# 05_SiC_Nanosecond_Stage.net
KiCad netlist of a schematic drawn in Altium Designer
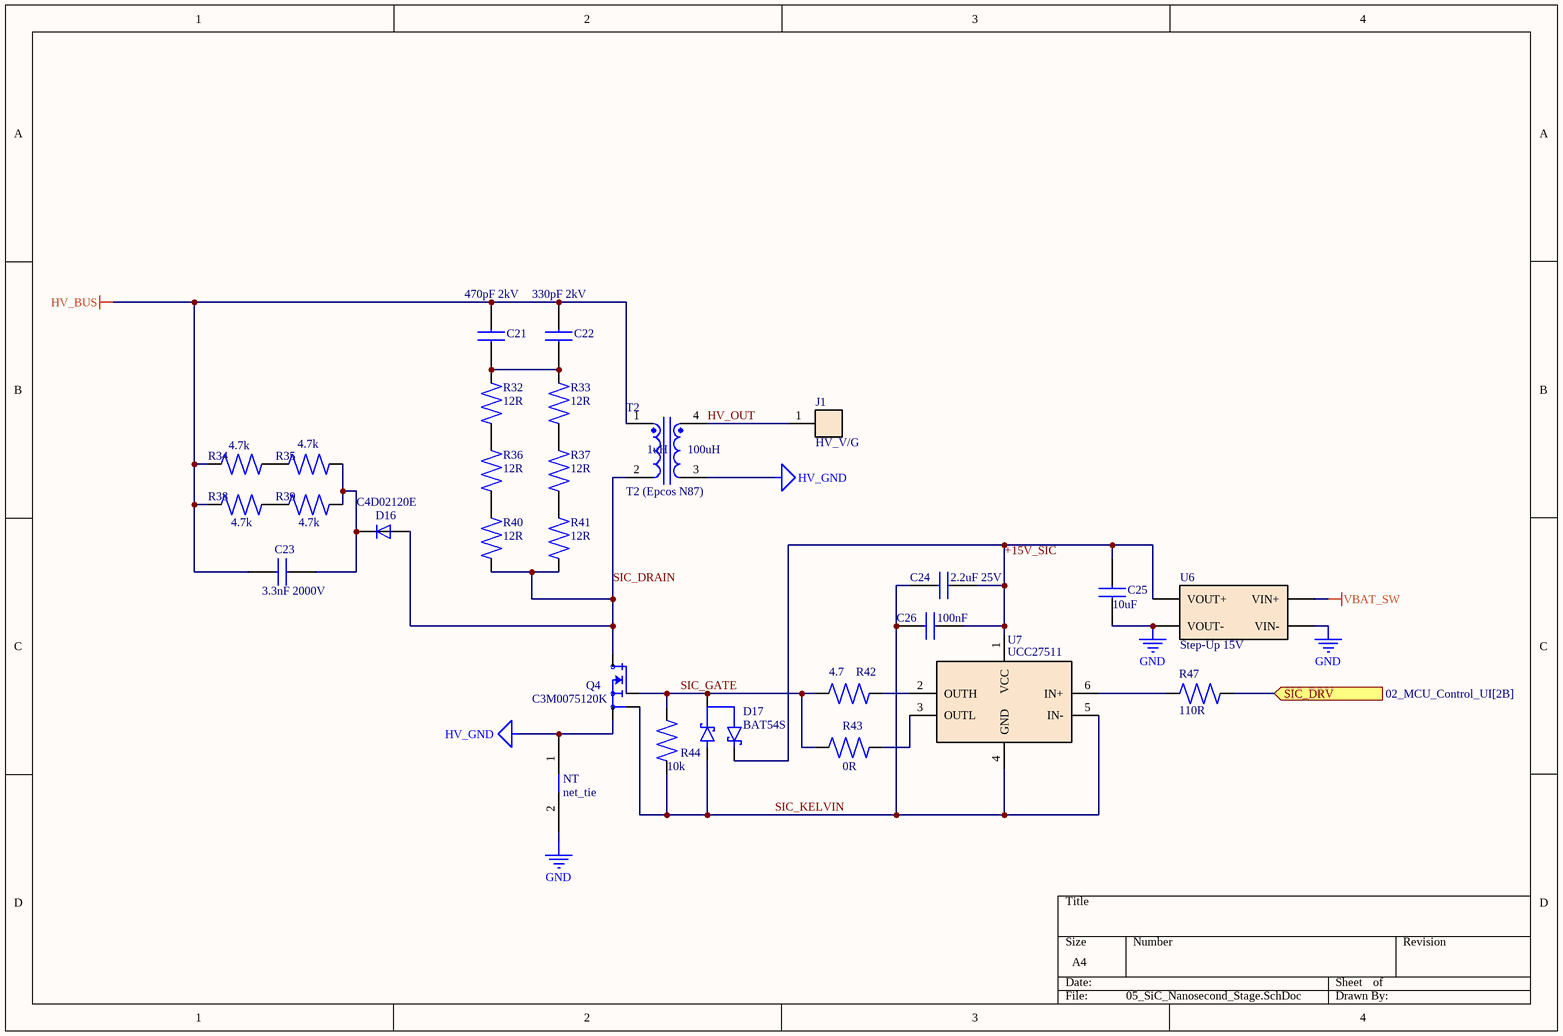
[diagram p0: 05_SiC_Nanosecond_Stage.SchDoc]

(export (version "E")
  (design (tool "Eeschema 10.0.6"))
  (components
    (comp (ref "C21")
      (value "470pF 2kV")
      (footprint "CAP_FILM_P15.0_CBB81_HEAVY_DUTY")
      (description "Capacitor Film, Polypropylene (PP), 470 pF, 2000 VDC, ±5%, Radial THT, Pitch 15mm, CBB81")
      (libsource (lib "Schlib1") (part "CAP_FILM_CBB81_470pF_2000V"))
    )
    (comp (ref "C22")
      (value "330pF 2kV")
      (footprint "CAP_FILM_P15.0_CBB81_HEAVY_DUTY")
      (description "Capacitor Film, Polypropylene (PP), 330 pF, 2000 VDC, ±5%, Radial THT, Pitch 15mm, CBB81")
      (libsource (lib "Schlib1") (part "CAP_FILM_CBB81_330pF_2000V"))
    )
    (comp (ref "C23")
      (value "3.3nF 2000V")
      (footprint "CAP_FILM_P15.0_CBB81_HEAVY_DUTY")
      (libsource (lib "Schlib1") (part "CAP_FILM_CBB81_3.2nF_2000V"))
    )
    (comp (ref "C24")
      (value "2.2uF 25V")
      (footprint "CHIP_0805_SMD")
      (description "Capacitor MLCC, Ceramic, 2.2 uF, 25 V, ±10%, X7R, SMD 0805, Hitano Enterprise")
      (libsource (lib "Schlib1") (part "CAP_0805_2.2uF_25V_X7R"))
    )
    (comp (ref "C25")
      (value "10uF")
      (footprint "CHIP_0805_SMD")
      (description "Capacitor MLCC, Ceramic, 10 uF, 16 V, ±10%, X7R, SMD 0805, Hitano Enterprise")
      (libsource (lib "Schlib1") (part "CAP_0805_10uF_16V_X7R"))
    )
    (comp (ref "C26")
      (value "100nF")
      (footprint "CHIP_0603_SMD")
      (description "Capacitor MLCC, Ceramic, 100 nF, 50 V, ±10%, X7R, SMD 0603, Samsung Electro-Mechanics")
      (libsource (lib "Schlib1") (part "CAP_0603_100nF_50V_X7R"))
    )
    (comp (ref "D16")
      (value "C4D02120E")
      (footprint "TO-252-2L_DPAK_THERMAL")
      (description "SiC Schottky Diode, 1200V, 2A, Zero Recovery, TO-252-2 (DPAK), Pin 1: Anode, Pin 2: Cathode (Tab)")
      (libsource (lib "Schlib1") (part "DIODE_SIC_C4D02120E_TO252"))
    )
    (comp (ref "D17")
      (value "BAT54S")
      (footprint "SOT-23_3P_SMD")
      (libsource (lib "Schlib1") (part "DIODE_SCHOTTKY_BAT54S_SOT23"))
    )
    (comp (ref "J1")
      (value "HV_V/G")
      (footprint "PAD_HV_UL3239_28AWG_ROUND")
      (description "High Voltage Solder Pad / Wire Terminal, Single Pin THT, Hole D=1.8mm, Pad D=3.5mm")
      (libsource (lib "Schlib1") (part "PAD_HV_TERMINAL_1P"))
    )
    (comp (ref "NT")
      (value "net_tie")
      (footprint "NET_TIE_SMD")
      (libsource (lib "Schlib1") (part "NET_TIE_SMD"))
    )
    (comp (ref "Q4")
      (value "C3M0075120K")
      (footprint "TO-247-4_WOLFSPEED_SLOTTED_VERT")
      (description "SiC Power MOSFET N-CH, 1200V, 30A, 75 mOhm, Kelvin Source, TO-247-4, Wolfspeed / Cree")
      (libsource (lib "Schlib1") (part "MOSFET_N-CH_C3M0075120K_TO247-4"))
    )
    (comp (ref "R32")
      (value "12R")
      (footprint "RES_2512_6.3x3.2_HANDSOLDER")
      (description "Resistor, 12 Ohm, ±5%, 1W, 200V, SMD 2512, High Power Pulse Snubber, Thick Film, UniOhm / Yageo")
      (libsource (lib "Schlib1") (part "RES_2512_12R_1W_5%"))
    )
    (comp (ref "R33")
      (value "12R")
      (footprint "RES_2512_6.3x3.2_HANDSOLDER")
      (description "Resistor, 12 Ohm, ±5%, 1W, 200V, SMD 2512, High Power Pulse Snubber, Thick Film, UniOhm / Yageo")
      (libsource (lib "Schlib1") (part "RES_2512_12R_1W_5%"))
    )
    (comp (ref "R34")
      (value "4.7k")
      (footprint "CHIP_1206_SMD")
      (description "Resistor, 4.7 kOhm, ±1%, 0.25W (1/4W), 200V, SMD 1206, Thick Film, Hitano")
      (libsource (lib "Schlib1") (part "RES_1206_4.7k_1%"))
    )
    (comp (ref "R35")
      (value "4.7k")
      (footprint "CHIP_1206_SMD")
      (description "Resistor, 4.7 kOhm, ±1%, 0.25W (1/4W), 200V, SMD 1206, Thick Film, Hitano")
      (libsource (lib "Schlib1") (part "RES_1206_4.7k_1%"))
    )
    (comp (ref "R36")
      (value "12R")
      (footprint "RES_2512_6.3x3.2_HANDSOLDER")
      (description "Resistor, 12 Ohm, ±5%, 1W, 200V, SMD 2512, High Power Pulse Snubber, Thick Film, UniOhm / Yageo")
      (libsource (lib "Schlib1") (part "RES_2512_12R_1W_5%"))
    )
    (comp (ref "R37")
      (value "12R")
      (footprint "RES_2512_6.3x3.2_HANDSOLDER")
      (description "Resistor, 12 Ohm, ±5%, 1W, 200V, SMD 2512, High Power Pulse Snubber, Thick Film, UniOhm / Yageo")
      (libsource (lib "Schlib1") (part "RES_2512_12R_1W_5%"))
    )
    (comp (ref "R38")
      (value "4.7k")
      (footprint "CHIP_1206_SMD")
      (description "Resistor, 4.7 kOhm, ±1%, 0.25W (1/4W), 200V, SMD 1206, Thick Film, Hitano")
      (libsource (lib "Schlib1") (part "RES_1206_4.7k_1%"))
    )
    (comp (ref "R39")
      (value "4.7k")
      (footprint "CHIP_1206_SMD")
      (description "Resistor, 4.7 kOhm, ±1%, 0.25W (1/4W), 200V, SMD 1206, Thick Film, Hitano")
      (libsource (lib "Schlib1") (part "RES_1206_4.7k_1%"))
    )
    (comp (ref "R40")
      (value "12R")
      (footprint "RES_2512_6.3x3.2_HANDSOLDER")
      (description "Resistor, 12 Ohm, ±5%, 1W, 200V, SMD 2512, High Power Pulse Snubber, Thick Film, UniOhm / Yageo")
      (libsource (lib "Schlib1") (part "RES_2512_12R_1W_5%"))
    )
    (comp (ref "R41")
      (value "12R")
      (footprint "RES_2512_6.3x3.2_HANDSOLDER")
      (description "Resistor, 12 Ohm, ±5%, 1W, 200V, SMD 2512, High Power Pulse Snubber, Thick Film, UniOhm / Yageo")
      (libsource (lib "Schlib1") (part "RES_2512_12R_1W_5%"))
    )
    (comp (ref "R42")
      (value "4.7")
      (footprint "CHIP_0603_SMD")
      (description "Resistor, 4.7 Ohm, ±5%, 0.1W (1/10W), 50V, SMD 0603, Gate Drive Series, KOME")
      (libsource (lib "Schlib1") (part "RES_0603_4R7"))
    )
    (comp (ref "R43")
      (value "0R")
      (footprint "CHIP_1206_SMD")
      (description "just in case")
      (libsource (lib "Schlib1") (part "RES_1206_0R"))
    )
    (comp (ref "R44")
      (value "10k")
      (footprint "CHIP_0603_SMD")
      (description "Resistor, 10 kOhm, ±1%, 0.1W (1/10W), 75V, SMD 0603, Thick Film, Hitano")
      (libsource (lib "Schlib1") (part "RES_0603_10k_1%"))
    )
    (comp (ref "R47")
      (value "110R")
      (footprint "CHIP_0805_SMD")
      (libsource (lib "Schlib1") (part "RES_0805_110R_0.1%"))
    )
    (comp (ref "T2")
      (value "T2 (Epcos N87)")
      (footprint "TRANS_AUTOTRANS_T2_EPCOS_R20_N87")
      (libsource (lib "Schlib1") (part "TRANS_AUTOTRANS_T2_N87"))
    )
    (comp (ref "U6")
      (value "Step-Up 15V")
      (footprint "MODULE_DC-DC_MT3608_BOOST_THT")
      (libsource (lib "Schlib1") (part "MODULE_DCDC_MT3608_STEP-UP"))
    )
    (comp (ref "U7")
      (value "UCC27511")
      (footprint "SOT-23-6_DBV_HANDSOLDER")
      (libsource (lib "Schlib1") (part "IC_GATE_DRIVER_UCC27511DBVR"))
    )
  )
  (nets
    (net (code "1") (name "/+15V_SIC") (class "Default")
      (node (ref "C24") (pin "1") (pinfunction "1_1") (pintype "passive"))
      (node (ref "C25") (pin "2") (pinfunction "2_2") (pintype "passive"))
      (node (ref "C26") (pin "1") (pinfunction "1_1") (pintype "passive"))
      (node (ref "D17") (pin "2") (pinfunction "K2_2") (pintype "passive"))
      (node (ref "U6") (pin "3") (pinfunction "VOUT+_3") (pintype "passive"))
      (node (ref "U7") (pin "1") (pinfunction "VCC_1") (pintype "power_in"))
    )
    (net (code "2") (name "/HV_OUT") (class "Default")
      (node (ref "J1") (pin "1") (pinfunction "1_1") (pintype "passive"))
      (node (ref "T2") (pin "4") (pinfunction "SEC+_4") (pintype "passive"))
    )
    (net (code "3") (name "/SIC_DRAIN") (class "Default")
      (node (ref "D16") (pin "1") (pinfunction "A_1") (pintype "passive"))
      (node (ref "Q4") (pin "1") (pinfunction "D_1") (pintype "passive"))
      (node (ref "R40") (pin "1") (pinfunction "1_1") (pintype "passive"))
      (node (ref "R41") (pin "1") (pinfunction "1_1") (pintype "passive"))
      (node (ref "T2") (pin "2") (pinfunction "DRAIN_2") (pintype "passive"))
    )
    (net (code "4") (name "/SIC_DRV") (class "Default")
      (node (ref "R47") (pin "2") (pinfunction "2_2") (pintype "passive"))
    )
    (net (code "5") (name "/SIC_GATE") (class "Default")
      (node (ref "D17") (pin "3") (pinfunction "K1+A2_3") (pintype "passive"))
      (node (ref "Q4") (pin "4") (pinfunction "G_4") (pintype "passive"))
      (node (ref "R42") (pin "1") (pinfunction "1_1") (pintype "passive"))
      (node (ref "R43") (pin "1") (pinfunction "1_1") (pintype "passive"))
      (node (ref "R44") (pin "2") (pinfunction "2_2") (pintype "passive"))
    )
    (net (code "6") (name "/SIC_KELVIN") (class "Default")
      (node (ref "C24") (pin "2") (pinfunction "2_2") (pintype "passive"))
      (node (ref "C26") (pin "2") (pinfunction "2_2") (pintype "passive"))
      (node (ref "D17") (pin "1") (pinfunction "A1_1") (pintype "passive"))
      (node (ref "Q4") (pin "3") (pinfunction "KS_3") (pintype "passive"))
      (node (ref "R44") (pin "1") (pinfunction "1_1") (pintype "passive"))
      (node (ref "U7") (pin "4") (pinfunction "GND_4") (pintype "passive"))
      (node (ref "U7") (pin "5") (pinfunction "IN-_5") (pintype "passive"))
    )
    (net (code "7") (name "GND") (class "Default")
      (node (ref "C25") (pin "1") (pinfunction "1_1") (pintype "passive"))
      (node (ref "NT") (pin "2") (pinfunction "2_2") (pintype "power_in"))
      (node (ref "U6") (pin "2") (pinfunction "VIN-_2") (pintype "passive"))
      (node (ref "U6") (pin "4") (pinfunction "VOUT-_4") (pintype "passive"))
    )
    (net (code "8") (name "HV_BUS") (class "Default")
      (node (ref "C21") (pin "2") (pinfunction "2_2") (pintype "passive"))
      (node (ref "C22") (pin "2") (pinfunction "2_2") (pintype "passive"))
      (node (ref "C23") (pin "1") (pinfunction "1_1") (pintype "passive"))
      (node (ref "R34") (pin "1") (pinfunction "1_1") (pintype "passive"))
      (node (ref "R38") (pin "1") (pinfunction "1_1") (pintype "passive"))
      (node (ref "T2") (pin "1") (pinfunction "+850V_1") (pintype "passive"))
    )
    (net (code "9") (name "HV_GND") (class "Default")
      (node (ref "NT") (pin "1") (pinfunction "1_1") (pintype "power_in"))
      (node (ref "Q4") (pin "2") (pinfunction "S_2") (pintype "passive"))
      (node (ref "T2") (pin "3") (pinfunction "HV_GND_3") (pintype "passive"))
    )
    (net (code "10") (name "Net-(C21-Pad1)") (class "Default")
      (node (ref "C21") (pin "1") (pinfunction "1_1") (pintype "passive"))
      (node (ref "C22") (pin "1") (pinfunction "1_1") (pintype "passive"))
      (node (ref "R32") (pin "2") (pinfunction "2_2") (pintype "passive"))
      (node (ref "R33") (pin "2") (pinfunction "2_2") (pintype "passive"))
    )
    (net (code "11") (name "Net-(D16-K)") (class "Default")
      (node (ref "C23") (pin "2") (pinfunction "2_2") (pintype "passive"))
      (node (ref "D16") (pin "2") (pinfunction "K_2") (pintype "passive"))
      (node (ref "R35") (pin "2") (pinfunction "2_2") (pintype "passive"))
      (node (ref "R39") (pin "2") (pinfunction "2_2") (pintype "passive"))
    )
    (net (code "12") (name "Net-(R32-Pad1)") (class "Default")
      (node (ref "R32") (pin "1") (pinfunction "1_1") (pintype "passive"))
      (node (ref "R36") (pin "2") (pinfunction "2_2") (pintype "passive"))
    )
    (net (code "13") (name "Net-(R33-Pad1)") (class "Default")
      (node (ref "R33") (pin "1") (pinfunction "1_1") (pintype "passive"))
      (node (ref "R37") (pin "2") (pinfunction "2_2") (pintype "passive"))
    )
    (net (code "14") (name "Net-(R34-Pad2)") (class "Default")
      (node (ref "R34") (pin "2") (pinfunction "2_2") (pintype "passive"))
      (node (ref "R35") (pin "1") (pinfunction "1_1") (pintype "passive"))
    )
    (net (code "15") (name "Net-(R36-Pad1)") (class "Default")
      (node (ref "R36") (pin "1") (pinfunction "1_1") (pintype "passive"))
      (node (ref "R40") (pin "2") (pinfunction "2_2") (pintype "passive"))
    )
    (net (code "16") (name "Net-(R37-Pad1)") (class "Default")
      (node (ref "R37") (pin "1") (pinfunction "1_1") (pintype "passive"))
      (node (ref "R41") (pin "2") (pinfunction "2_2") (pintype "passive"))
    )
    (net (code "17") (name "Net-(R38-Pad2)") (class "Default")
      (node (ref "R38") (pin "2") (pinfunction "2_2") (pintype "passive"))
      (node (ref "R39") (pin "1") (pinfunction "1_1") (pintype "passive"))
    )
    (net (code "18") (name "Net-(U7-IN+)") (class "Default")
      (node (ref "R47") (pin "1") (pinfunction "1_1") (pintype "passive"))
      (node (ref "U7") (pin "6") (pinfunction "IN+_6") (pintype "passive"))
    )
    (net (code "19") (name "Net-(U7-OUTH)") (class "Default")
      (node (ref "R42") (pin "2") (pinfunction "2_2") (pintype "passive"))
      (node (ref "U7") (pin "2") (pinfunction "OUTH_2") (pintype "passive"))
    )
    (net (code "20") (name "Net-(U7-OUTL)") (class "Default")
      (node (ref "R43") (pin "2") (pinfunction "2_2") (pintype "passive"))
      (node (ref "U7") (pin "3") (pinfunction "OUTL_3") (pintype "passive"))
    )
    (net (code "21") (name "VBAT_SW") (class "Default")
      (node (ref "U6") (pin "1") (pinfunction "VIN+_1") (pintype "passive"))
    )
  )
)
